# Isolated_DAC.net
KiCad netlist of a schematic drawn in Altium Designer
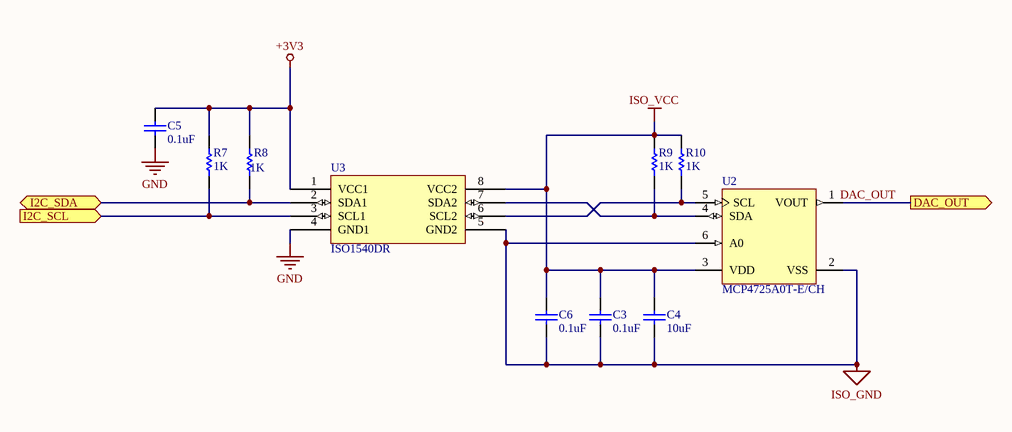
[diagram p0: Isolated DAC.SchDoc]

(export (version "E")
  (design (tool "Eeschema 10.0.6"))
  (components
    (comp (ref "C3")
      (value "0.1uF")
      (footprint "CAPC1608X87X35NL15T15")
      (fields (field (name "PART NUMBER") "C0603X104K5RACTU") (field (name "MANUFACTURER") "Kemet"))
      (libsource (lib "Altium Content Vault") (part "CAP"))
    )
    (comp (ref "C4")
      (value "10uF")
      (footprint "CAPC1608X90X35NL10T15")
      (fields (field (name "PART NUMBER") "GRM188R60J106ME47D") (field (name "MANUFACTURER") "Murata"))
      (libsource (lib "Altium Content Vault") (part "CAP"))
    )
    (comp (ref "C5")
      (value "0.1uF")
      (footprint "CAPC1608X87X35NL15T15")
      (fields (field (name "PART NUMBER") "C0603X104K5RACTU") (field (name "MANUFACTURER") "Kemet"))
      (libsource (lib "Altium Content Vault") (part "CAP"))
    )
    (comp (ref "C6")
      (value "0.1uF")
      (footprint "CAPC1608X87X35NL15T15")
      (fields (field (name "PART NUMBER") "C0603X104K5RACTU") (field (name "MANUFACTURER") "Kemet"))
      (libsource (lib "Altium Content Vault") (part "CAP"))
    )
    (comp (ref "R7")
      (value "1K")
      (footprint "RESC1608X55X30LL15T15")
      (fields (field (name "PART NUMBER") "ERJ-3EKF1001V") (field (name "MANUFACTURER") "Panasonic"))
      (libsource (lib "Altium Content Vault") (part "RES"))
    )
    (comp (ref "R8")
      (value "1K")
      (footprint "RESC1608X55X30LL15T15")
      (fields (field (name "PART NUMBER") "ERJ-3EKF1001V") (field (name "MANUFACTURER") "Panasonic"))
      (libsource (lib "Altium Content Vault") (part "RES"))
    )
    (comp (ref "R9")
      (value "1K")
      (footprint "RESC1608X55X30LL15T15")
      (fields (field (name "PART NUMBER") "ERJ-3EKF1001V") (field (name "MANUFACTURER") "Panasonic"))
      (libsource (lib "Altium Content Vault") (part "RES"))
    )
    (comp (ref "R10")
      (value "1K")
      (footprint "RESC1608X55X30LL15T15")
      (fields (field (name "PART NUMBER") "ERJ-3EKF1001V") (field (name "MANUFACTURER") "Panasonic"))
      (libsource (lib "Altium Content Vault") (part "RES"))
    )
    (comp (ref "U2")
      (value "MCP4725A0T-E/CH")
      (footprint "SOT-23-CH6_L")
      (libsource (lib "Altium Content Vault") (part "CON-DAC-MCP4725-6"))
    )
    (comp (ref "U3")
      (value "ISO1540DR")
      (footprint "ISO1540DR SOIC127P600X175-8N")
      (description "DGTL ISO 2.5KV 2CH I2C 8SOIC")
      (libsource (lib "cpd") (part "ISO1540DR"))
    )
  )
  (nets
    (net (code "1") (name "+3V3") (class "Default")
      (node (ref "C5") (pin "1") (pinfunction "1_1") (pintype "passive"))
      (node (ref "R7") (pin "2") (pinfunction "2_2") (pintype "passive"))
      (node (ref "R8") (pin "2") (pinfunction "2_2") (pintype "passive"))
      (node (ref "U3") (pin "1") (pinfunction "VCC1_1") (pintype "power_in"))
    )
    (net (code "2") (name "/DAC_OUT") (class "Default")
      (node (ref "U2") (pin "1") (pinfunction "VOUT_1") (pintype "output"))
    )
    (net (code "3") (name "/I2C_SCL") (class "Default")
      (node (ref "R7") (pin "1") (pinfunction "1_1") (pintype "passive"))
      (node (ref "U3") (pin "3") (pinfunction "SCL1_3") (pintype "bidirectional"))
    )
    (net (code "4") (name "/I2C_SDA") (class "Default")
      (node (ref "R8") (pin "1") (pinfunction "1_1") (pintype "passive"))
      (node (ref "U3") (pin "2") (pinfunction "SDA1_2") (pintype "bidirectional"))
    )
    (net (code "5") (name "GND") (class "Default")
      (node (ref "C5") (pin "2") (pinfunction "2_2") (pintype "passive"))
      (node (ref "U3") (pin "4") (pinfunction "GND1_4") (pintype "power_in"))
    )
    (net (code "6") (name "ISO_GND") (class "Default")
      (node (ref "C3") (pin "2") (pinfunction "2_2") (pintype "passive"))
      (node (ref "C4") (pin "1") (pinfunction "1_1") (pintype "passive"))
      (node (ref "C6") (pin "2") (pinfunction "2_2") (pintype "passive"))
      (node (ref "U2") (pin "2") (pinfunction "VSS_2") (pintype "power_in"))
      (node (ref "U2") (pin "6") (pinfunction "A0_6") (pintype "input"))
      (node (ref "U3") (pin "5") (pinfunction "GND2_5") (pintype "power_in"))
    )
    (net (code "7") (name "ISO_VCC") (class "Default")
      (node (ref "C3") (pin "1") (pinfunction "1_1") (pintype "passive"))
      (node (ref "C4") (pin "2") (pinfunction "2_2") (pintype "passive"))
      (node (ref "C6") (pin "1") (pinfunction "1_1") (pintype "passive"))
      (node (ref "R10") (pin "2") (pinfunction "2_2") (pintype "passive"))
      (node (ref "R9") (pin "2") (pinfunction "2_2") (pintype "passive"))
      (node (ref "U2") (pin "3") (pinfunction "VDD_3") (pintype "power_in"))
      (node (ref "U3") (pin "8") (pinfunction "VCC2_8") (pintype "passive"))
    )
    (net (code "8") (name "Net-(U2-SCL)") (class "Default")
      (node (ref "R10") (pin "1") (pinfunction "1_1") (pintype "passive"))
      (node (ref "U2") (pin "5") (pinfunction "SCL_5") (pintype "input"))
      (node (ref "U3") (pin "6") (pinfunction "SCL2_6") (pintype "bidirectional"))
    )
    (net (code "9") (name "Net-(U2-SDA)") (class "Default")
      (node (ref "R9") (pin "1") (pinfunction "1_1") (pintype "passive"))
      (node (ref "U2") (pin "4") (pinfunction "SDA_4") (pintype "bidirectional"))
      (node (ref "U3") (pin "7") (pinfunction "SDA2_7") (pintype "bidirectional"))
    )
  )
)
